# HighVBoard_01.net
KiCad netlist of a schematic drawn in EAGLE
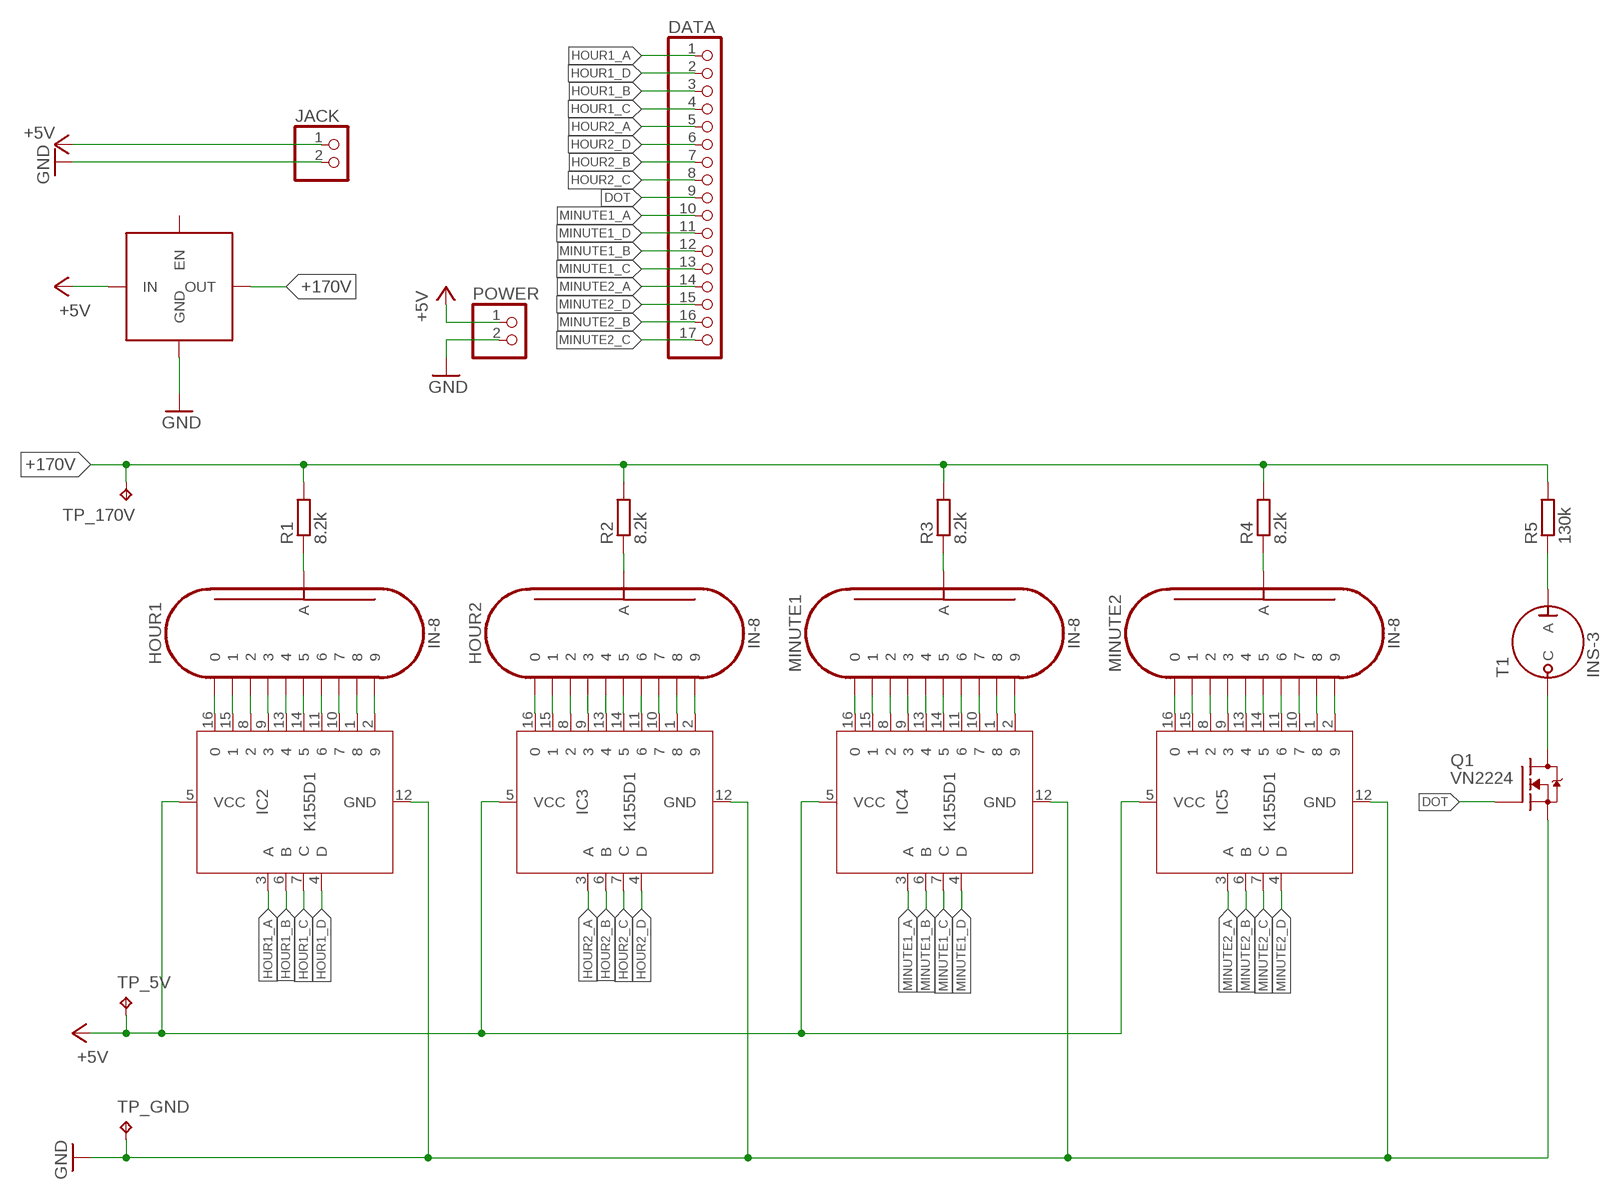
[diagram p0: schematic, sheet 1]

(export (version "E")
  (design (tool "Eeschema 10.0.6"))
  (components
    (comp (ref "DATA")
      (value "PINHD-1X17")
      (footprint "eagle-import:1X17")
      (libsource (lib "eagle-import") (part "PINHD-1X17"))
    )
    (comp (ref "HOUR1")
      (value "IN-8")
      (footprint "eagle-import:IN-8")
      (libsource (lib "eagle-import") (part "IN-8"))
    )
    (comp (ref "HOUR2")
      (value "IN-8")
      (footprint "eagle-import:IN-8")
      (libsource (lib "eagle-import") (part "IN-8"))
    )
    (comp (ref "IC2")
      (value "K155D1")
      (footprint "eagle-import:DIL16")
      (libsource (lib "eagle-import") (part "K155D1"))
    )
    (comp (ref "IC3")
      (value "K155D1")
      (footprint "eagle-import:DIL16")
      (libsource (lib "eagle-import") (part "K155D1"))
    )
    (comp (ref "IC4")
      (value "K155D1")
      (footprint "eagle-import:DIL16")
      (libsource (lib "eagle-import") (part "K155D1"))
    )
    (comp (ref "IC5")
      (value "K155D1")
      (footprint "eagle-import:DIL16")
      (libsource (lib "eagle-import") (part "K155D1"))
    )
    (comp (ref "JACK")
      (value "PINHD-1X2/90")
      (footprint "eagle-import:1X02_90")
      (libsource (lib "eagle-import") (part "PINHD-1X2/90"))
    )
    (comp (ref "MINUTE1")
      (value "IN-8")
      (footprint "eagle-import:IN-8")
      (libsource (lib "eagle-import") (part "IN-8"))
    )
    (comp (ref "MINUTE2")
      (value "IN-8")
      (footprint "eagle-import:IN-8")
      (libsource (lib "eagle-import") (part "IN-8"))
    )
    (comp (ref "POWER")
      (value "PINHD-1X2")
      (footprint "eagle-import:1X02")
      (libsource (lib "eagle-import") (part "PINHD-1X2"))
    )
    (comp (ref "Q1")
      (value "VN2224")
      (footprint "eagle-import:TO92")
      (libsource (lib "eagle-import") (part "VN2224"))
    )
    (comp (ref "R1")
      (value "8.2k")
      (footprint "eagle-import:0207_10")
      (libsource (lib "eagle-import") (part "R-EU_0207/10"))
    )
    (comp (ref "R2")
      (value "8.2k")
      (footprint "eagle-import:0207_10")
      (libsource (lib "eagle-import") (part "R-EU_0207/10"))
    )
    (comp (ref "R3")
      (value "8.2k")
      (footprint "eagle-import:0207_10")
      (libsource (lib "eagle-import") (part "R-EU_0207/10"))
    )
    (comp (ref "R4")
      (value "8.2k")
      (footprint "eagle-import:0207_10")
      (libsource (lib "eagle-import") (part "R-EU_0207/10"))
    )
    (comp (ref "R5")
      (value "130k")
      (footprint "eagle-import:0207_10")
      (libsource (lib "eagle-import") (part "R-EU_0207/10"))
    )
    (comp (ref "T1")
      (value "INS-3")
      (footprint "eagle-import:INS-3")
      (libsource (lib "eagle-import") (part "INS-3"))
    )
    (comp (ref "TP_5V")
      (value "TPPAD1-13")
      (footprint "eagle-import:P1-13")
      (libsource (lib "eagle-import") (part "TPPAD1-13"))
    )
    (comp (ref "TP_170V")
      (value "TPPAD1-13")
      (footprint "eagle-import:P1-13")
      (libsource (lib "eagle-import") (part "TPPAD1-13"))
    )
    (comp (ref "TP_GND")
      (value "TPPAD1-13")
      (footprint "eagle-import:P1-13")
      (libsource (lib "eagle-import") (part "TPPAD1-13"))
    )
    (comp (ref "U$1")
      (value "NIXIE-PSU")
      (footprint "eagle-import:NIXIE-PSU")
      (libsource (lib "eagle-import") (part "NIXIE-PSU"))
    )
  )
  (nets
    (net (code "1") (name "+5V") (class "Default")
      (node (ref "IC2") (pin "5") (pinfunction "VCC_5") (pintype "bidirectional"))
      (node (ref "IC3") (pin "5") (pinfunction "VCC_5") (pintype "bidirectional"))
      (node (ref "IC4") (pin "5") (pinfunction "VCC_5") (pintype "bidirectional"))
      (node (ref "IC5") (pin "5") (pinfunction "VCC_5") (pintype "bidirectional"))
      (node (ref "JACK") (pin "1") (pinfunction "1_1") (pintype "passive"))
      (node (ref "POWER") (pin "1") (pinfunction "1_1") (pintype "passive"))
      (node (ref "TP_5V") (pin "TP") (pinfunction "TP_TP") (pintype "input"))
      (node (ref "U$1") (pin "1") (pinfunction "IN_1") (pintype "bidirectional"))
    )
    (net (code "2") (name "+170V") (class "Default")
      (node (ref "R1") (pin "2") (pinfunction "2_2") (pintype "passive"))
      (node (ref "R2") (pin "2") (pinfunction "2_2") (pintype "passive"))
      (node (ref "R3") (pin "2") (pinfunction "2_2") (pintype "passive"))
      (node (ref "R4") (pin "2") (pinfunction "2_2") (pintype "passive"))
      (node (ref "R5") (pin "2") (pinfunction "2_2") (pintype "passive"))
      (node (ref "TP_170V") (pin "TP") (pinfunction "TP_TP") (pintype "input"))
      (node (ref "U$1") (pin "5") (pinfunction "OUT_5") (pintype "bidirectional"))
    )
    (net (code "3") (name "DOT") (class "Default")
      (node (ref "DATA") (pin "9") (pinfunction "9_9") (pintype "passive"))
      (node (ref "Q1") (pin "2") (pinfunction "G_2") (pintype "passive"))
    )
    (net (code "4") (name "GND") (class "Default")
      (node (ref "IC2") (pin "12") (pinfunction "GND_12") (pintype "bidirectional"))
      (node (ref "IC3") (pin "12") (pinfunction "GND_12") (pintype "bidirectional"))
      (node (ref "IC4") (pin "12") (pinfunction "GND_12") (pintype "bidirectional"))
      (node (ref "IC5") (pin "12") (pinfunction "GND_12") (pintype "bidirectional"))
      (node (ref "JACK") (pin "2") (pinfunction "2_2") (pintype "passive"))
      (node (ref "POWER") (pin "2") (pinfunction "2_2") (pintype "passive"))
      (node (ref "Q1") (pin "1") (pinfunction "S_1") (pintype "passive"))
      (node (ref "TP_GND") (pin "TP") (pinfunction "TP_TP") (pintype "input"))
      (node (ref "U$1") (pin "2") (pinfunction "GND_2") (pintype "bidirectional"))
      (node (ref "U$1") (pin "4") (pinfunction "GND_4") (pintype "bidirectional"))
    )
    (net (code "5") (name "HOUR1_A") (class "Default")
      (node (ref "DATA") (pin "1") (pinfunction "1_1") (pintype "passive"))
      (node (ref "IC2") (pin "3") (pinfunction "A_3") (pintype "bidirectional"))
    )
    (net (code "6") (name "HOUR1_B") (class "Default")
      (node (ref "DATA") (pin "3") (pinfunction "3_3") (pintype "passive"))
      (node (ref "IC2") (pin "6") (pinfunction "B_6") (pintype "bidirectional"))
    )
    (net (code "7") (name "HOUR1_C") (class "Default")
      (node (ref "DATA") (pin "4") (pinfunction "4_4") (pintype "passive"))
      (node (ref "IC2") (pin "7") (pinfunction "C_7") (pintype "bidirectional"))
    )
    (net (code "8") (name "HOUR1_D") (class "Default")
      (node (ref "DATA") (pin "2") (pinfunction "2_2") (pintype "passive"))
      (node (ref "IC2") (pin "4") (pinfunction "D_4") (pintype "bidirectional"))
    )
    (net (code "9") (name "HOUR2_A") (class "Default")
      (node (ref "DATA") (pin "5") (pinfunction "5_5") (pintype "passive"))
      (node (ref "IC3") (pin "3") (pinfunction "A_3") (pintype "bidirectional"))
    )
    (net (code "10") (name "HOUR2_B") (class "Default")
      (node (ref "DATA") (pin "7") (pinfunction "7_7") (pintype "passive"))
      (node (ref "IC3") (pin "6") (pinfunction "B_6") (pintype "bidirectional"))
    )
    (net (code "11") (name "HOUR2_C") (class "Default")
      (node (ref "DATA") (pin "8") (pinfunction "8_8") (pintype "passive"))
      (node (ref "IC3") (pin "7") (pinfunction "C_7") (pintype "bidirectional"))
    )
    (net (code "12") (name "HOUR2_D") (class "Default")
      (node (ref "DATA") (pin "6") (pinfunction "6_6") (pintype "passive"))
      (node (ref "IC3") (pin "4") (pinfunction "D_4") (pintype "bidirectional"))
    )
    (net (code "13") (name "MINUTE1_A") (class "Default")
      (node (ref "DATA") (pin "10") (pinfunction "10_10") (pintype "passive"))
      (node (ref "IC4") (pin "3") (pinfunction "A_3") (pintype "bidirectional"))
    )
    (net (code "14") (name "MINUTE1_B") (class "Default")
      (node (ref "DATA") (pin "12") (pinfunction "12_12") (pintype "passive"))
      (node (ref "IC4") (pin "6") (pinfunction "B_6") (pintype "bidirectional"))
    )
    (net (code "15") (name "MINUTE1_C") (class "Default")
      (node (ref "DATA") (pin "13") (pinfunction "13_13") (pintype "passive"))
      (node (ref "IC4") (pin "7") (pinfunction "C_7") (pintype "bidirectional"))
    )
    (net (code "16") (name "MINUTE1_D") (class "Default")
      (node (ref "DATA") (pin "11") (pinfunction "11_11") (pintype "passive"))
      (node (ref "IC4") (pin "4") (pinfunction "D_4") (pintype "bidirectional"))
    )
    (net (code "17") (name "MINUTE2_A") (class "Default")
      (node (ref "DATA") (pin "14") (pinfunction "14_14") (pintype "passive"))
      (node (ref "IC5") (pin "3") (pinfunction "A_3") (pintype "bidirectional"))
    )
    (net (code "18") (name "MINUTE2_B") (class "Default")
      (node (ref "DATA") (pin "16") (pinfunction "16_16") (pintype "passive"))
      (node (ref "IC5") (pin "6") (pinfunction "B_6") (pintype "bidirectional"))
    )
    (net (code "19") (name "MINUTE2_C") (class "Default")
      (node (ref "DATA") (pin "17") (pinfunction "17_17") (pintype "passive"))
      (node (ref "IC5") (pin "7") (pinfunction "C_7") (pintype "bidirectional"))
    )
    (net (code "20") (name "MINUTE2_D") (class "Default")
      (node (ref "DATA") (pin "15") (pinfunction "15_15") (pintype "passive"))
      (node (ref "IC5") (pin "4") (pinfunction "D_4") (pintype "bidirectional"))
    )
    (net (code "21") (name "Net-(HOUR1-0)") (class "Default")
      (node (ref "HOUR1") (pin "10") (pinfunction "0_10") (pintype "bidirectional"))
      (node (ref "IC2") (pin "16") (pinfunction "0_16") (pintype "bidirectional"))
    )
    (net (code "22") (name "Net-(HOUR1-PadA)") (class "Default")
      (node (ref "HOUR1") (pin "A") (pinfunction "A_A") (pintype "bidirectional"))
      (node (ref "R1") (pin "1") (pinfunction "1_1") (pintype "passive"))
    )
    (net (code "23") (name "Net-(HOUR2-0)") (class "Default")
      (node (ref "HOUR2") (pin "10") (pinfunction "0_10") (pintype "bidirectional"))
      (node (ref "IC3") (pin "16") (pinfunction "0_16") (pintype "bidirectional"))
    )
    (net (code "24") (name "Net-(HOUR2-PadA)") (class "Default")
      (node (ref "HOUR2") (pin "A") (pinfunction "A_A") (pintype "bidirectional"))
      (node (ref "R2") (pin "1") (pinfunction "1_1") (pintype "passive"))
    )
    (net (code "25") (name "Net-(IC2-1)") (class "Default")
      (node (ref "HOUR1") (pin "1") (pinfunction "1_1") (pintype "bidirectional"))
      (node (ref "IC2") (pin "15") (pinfunction "1_15") (pintype "bidirectional"))
    )
    (net (code "26") (name "Net-(IC2-2)") (class "Default")
      (node (ref "HOUR1") (pin "2") (pinfunction "2_2") (pintype "bidirectional"))
      (node (ref "IC2") (pin "8") (pinfunction "2_8") (pintype "bidirectional"))
    )
    (net (code "27") (name "Net-(IC2-3)") (class "Default")
      (node (ref "HOUR1") (pin "3") (pinfunction "3_3") (pintype "bidirectional"))
      (node (ref "IC2") (pin "9") (pinfunction "3_9") (pintype "bidirectional"))
    )
    (net (code "28") (name "Net-(IC2-4)") (class "Default")
      (node (ref "HOUR1") (pin "4") (pinfunction "4_4") (pintype "bidirectional"))
      (node (ref "IC2") (pin "13") (pinfunction "4_13") (pintype "bidirectional"))
    )
    (net (code "29") (name "Net-(IC2-5)") (class "Default")
      (node (ref "HOUR1") (pin "5") (pinfunction "5_5") (pintype "bidirectional"))
      (node (ref "IC2") (pin "14") (pinfunction "5_14") (pintype "bidirectional"))
    )
    (net (code "30") (name "Net-(IC2-6)") (class "Default")
      (node (ref "HOUR1") (pin "6") (pinfunction "6_6") (pintype "bidirectional"))
      (node (ref "IC2") (pin "11") (pinfunction "6_11") (pintype "bidirectional"))
    )
    (net (code "31") (name "Net-(IC2-7)") (class "Default")
      (node (ref "HOUR1") (pin "7") (pinfunction "7_7") (pintype "bidirectional"))
      (node (ref "IC2") (pin "10") (pinfunction "7_10") (pintype "bidirectional"))
    )
    (net (code "32") (name "Net-(IC2-8)") (class "Default")
      (node (ref "HOUR1") (pin "8") (pinfunction "8_8") (pintype "bidirectional"))
      (node (ref "IC2") (pin "1") (pinfunction "8_1") (pintype "bidirectional"))
    )
    (net (code "33") (name "Net-(IC2-9)") (class "Default")
      (node (ref "HOUR1") (pin "9") (pinfunction "9_9") (pintype "bidirectional"))
      (node (ref "IC2") (pin "2") (pinfunction "9_2") (pintype "bidirectional"))
    )
    (net (code "34") (name "Net-(IC3-1)") (class "Default")
      (node (ref "HOUR2") (pin "1") (pinfunction "1_1") (pintype "bidirectional"))
      (node (ref "IC3") (pin "15") (pinfunction "1_15") (pintype "bidirectional"))
    )
    (net (code "35") (name "Net-(IC3-2)") (class "Default")
      (node (ref "HOUR2") (pin "2") (pinfunction "2_2") (pintype "bidirectional"))
      (node (ref "IC3") (pin "8") (pinfunction "2_8") (pintype "bidirectional"))
    )
    (net (code "36") (name "Net-(IC3-3)") (class "Default")
      (node (ref "HOUR2") (pin "3") (pinfunction "3_3") (pintype "bidirectional"))
      (node (ref "IC3") (pin "9") (pinfunction "3_9") (pintype "bidirectional"))
    )
    (net (code "37") (name "Net-(IC3-4)") (class "Default")
      (node (ref "HOUR2") (pin "4") (pinfunction "4_4") (pintype "bidirectional"))
      (node (ref "IC3") (pin "13") (pinfunction "4_13") (pintype "bidirectional"))
    )
    (net (code "38") (name "Net-(IC3-5)") (class "Default")
      (node (ref "HOUR2") (pin "5") (pinfunction "5_5") (pintype "bidirectional"))
      (node (ref "IC3") (pin "14") (pinfunction "5_14") (pintype "bidirectional"))
    )
    (net (code "39") (name "Net-(IC3-6)") (class "Default")
      (node (ref "HOUR2") (pin "6") (pinfunction "6_6") (pintype "bidirectional"))
      (node (ref "IC3") (pin "11") (pinfunction "6_11") (pintype "bidirectional"))
    )
    (net (code "40") (name "Net-(IC3-7)") (class "Default")
      (node (ref "HOUR2") (pin "7") (pinfunction "7_7") (pintype "bidirectional"))
      (node (ref "IC3") (pin "10") (pinfunction "7_10") (pintype "bidirectional"))
    )
    (net (code "41") (name "Net-(IC3-8)") (class "Default")
      (node (ref "HOUR2") (pin "8") (pinfunction "8_8") (pintype "bidirectional"))
      (node (ref "IC3") (pin "1") (pinfunction "8_1") (pintype "bidirectional"))
    )
    (net (code "42") (name "Net-(IC3-9)") (class "Default")
      (node (ref "HOUR2") (pin "9") (pinfunction "9_9") (pintype "bidirectional"))
      (node (ref "IC3") (pin "2") (pinfunction "9_2") (pintype "bidirectional"))
    )
    (net (code "43") (name "Net-(IC4-0)") (class "Default")
      (node (ref "IC4") (pin "16") (pinfunction "0_16") (pintype "bidirectional"))
      (node (ref "MINUTE1") (pin "10") (pinfunction "0_10") (pintype "bidirectional"))
    )
    (net (code "44") (name "Net-(IC4-1)") (class "Default")
      (node (ref "IC4") (pin "15") (pinfunction "1_15") (pintype "bidirectional"))
      (node (ref "MINUTE1") (pin "1") (pinfunction "1_1") (pintype "bidirectional"))
    )
    (net (code "45") (name "Net-(IC4-2)") (class "Default")
      (node (ref "IC4") (pin "8") (pinfunction "2_8") (pintype "bidirectional"))
      (node (ref "MINUTE1") (pin "2") (pinfunction "2_2") (pintype "bidirectional"))
    )
    (net (code "46") (name "Net-(IC4-3)") (class "Default")
      (node (ref "IC4") (pin "9") (pinfunction "3_9") (pintype "bidirectional"))
      (node (ref "MINUTE1") (pin "3") (pinfunction "3_3") (pintype "bidirectional"))
    )
    (net (code "47") (name "Net-(IC4-4)") (class "Default")
      (node (ref "IC4") (pin "13") (pinfunction "4_13") (pintype "bidirectional"))
      (node (ref "MINUTE1") (pin "4") (pinfunction "4_4") (pintype "bidirectional"))
    )
    (net (code "48") (name "Net-(IC4-5)") (class "Default")
      (node (ref "IC4") (pin "14") (pinfunction "5_14") (pintype "bidirectional"))
      (node (ref "MINUTE1") (pin "5") (pinfunction "5_5") (pintype "bidirectional"))
    )
    (net (code "49") (name "Net-(IC4-6)") (class "Default")
      (node (ref "IC4") (pin "11") (pinfunction "6_11") (pintype "bidirectional"))
      (node (ref "MINUTE1") (pin "6") (pinfunction "6_6") (pintype "bidirectional"))
    )
    (net (code "50") (name "Net-(IC4-7)") (class "Default")
      (node (ref "IC4") (pin "10") (pinfunction "7_10") (pintype "bidirectional"))
      (node (ref "MINUTE1") (pin "7") (pinfunction "7_7") (pintype "bidirectional"))
    )
    (net (code "51") (name "Net-(IC4-8)") (class "Default")
      (node (ref "IC4") (pin "1") (pinfunction "8_1") (pintype "bidirectional"))
      (node (ref "MINUTE1") (pin "8") (pinfunction "8_8") (pintype "bidirectional"))
    )
    (net (code "52") (name "Net-(IC4-9)") (class "Default")
      (node (ref "IC4") (pin "2") (pinfunction "9_2") (pintype "bidirectional"))
      (node (ref "MINUTE1") (pin "9") (pinfunction "9_9") (pintype "bidirectional"))
    )
    (net (code "53") (name "Net-(IC5-0)") (class "Default")
      (node (ref "IC5") (pin "16") (pinfunction "0_16") (pintype "bidirectional"))
      (node (ref "MINUTE2") (pin "10") (pinfunction "0_10") (pintype "bidirectional"))
    )
    (net (code "54") (name "Net-(IC5-1)") (class "Default")
      (node (ref "IC5") (pin "15") (pinfunction "1_15") (pintype "bidirectional"))
      (node (ref "MINUTE2") (pin "1") (pinfunction "1_1") (pintype "bidirectional"))
    )
    (net (code "55") (name "Net-(IC5-2)") (class "Default")
      (node (ref "IC5") (pin "8") (pinfunction "2_8") (pintype "bidirectional"))
      (node (ref "MINUTE2") (pin "2") (pinfunction "2_2") (pintype "bidirectional"))
    )
    (net (code "56") (name "Net-(IC5-3)") (class "Default")
      (node (ref "IC5") (pin "9") (pinfunction "3_9") (pintype "bidirectional"))
      (node (ref "MINUTE2") (pin "3") (pinfunction "3_3") (pintype "bidirectional"))
    )
    (net (code "57") (name "Net-(IC5-4)") (class "Default")
      (node (ref "IC5") (pin "13") (pinfunction "4_13") (pintype "bidirectional"))
      (node (ref "MINUTE2") (pin "4") (pinfunction "4_4") (pintype "bidirectional"))
    )
    (net (code "58") (name "Net-(IC5-5)") (class "Default")
      (node (ref "IC5") (pin "14") (pinfunction "5_14") (pintype "bidirectional"))
      (node (ref "MINUTE2") (pin "5") (pinfunction "5_5") (pintype "bidirectional"))
    )
    (net (code "59") (name "Net-(IC5-6)") (class "Default")
      (node (ref "IC5") (pin "11") (pinfunction "6_11") (pintype "bidirectional"))
      (node (ref "MINUTE2") (pin "6") (pinfunction "6_6") (pintype "bidirectional"))
    )
    (net (code "60") (name "Net-(IC5-7)") (class "Default")
      (node (ref "IC5") (pin "10") (pinfunction "7_10") (pintype "bidirectional"))
      (node (ref "MINUTE2") (pin "7") (pinfunction "7_7") (pintype "bidirectional"))
    )
    (net (code "61") (name "Net-(IC5-8)") (class "Default")
      (node (ref "IC5") (pin "1") (pinfunction "8_1") (pintype "bidirectional"))
      (node (ref "MINUTE2") (pin "8") (pinfunction "8_8") (pintype "bidirectional"))
    )
    (net (code "62") (name "Net-(IC5-9)") (class "Default")
      (node (ref "IC5") (pin "2") (pinfunction "9_2") (pintype "bidirectional"))
      (node (ref "MINUTE2") (pin "9") (pinfunction "9_9") (pintype "bidirectional"))
    )
    (net (code "63") (name "Net-(MINUTE1-PadA)") (class "Default")
      (node (ref "MINUTE1") (pin "A") (pinfunction "A_A") (pintype "bidirectional"))
      (node (ref "R3") (pin "1") (pinfunction "1_1") (pintype "passive"))
    )
    (net (code "64") (name "Net-(MINUTE2-PadA)") (class "Default")
      (node (ref "MINUTE2") (pin "A") (pinfunction "A_A") (pintype "bidirectional"))
      (node (ref "R4") (pin "1") (pinfunction "1_1") (pintype "passive"))
    )
    (net (code "65") (name "Net-(Q1-D)") (class "Default")
      (node (ref "Q1") (pin "3") (pinfunction "D_3") (pintype "passive"))
      (node (ref "T1") (pin "C") (pinfunction "C_C") (pintype "bidirectional"))
    )
    (net (code "66") (name "Net-(R5-Pad1)") (class "Default")
      (node (ref "R5") (pin "1") (pinfunction "1_1") (pintype "passive"))
      (node (ref "T1") (pin "A") (pinfunction "A_A") (pintype "bidirectional"))
    )
    (net (code "67") (name "unconnected-(U$1-EN-Pad3)") (class "Default")
      (node (ref "U$1") (pin "3") (pinfunction "EN_3") (pintype "bidirectional"))
    )
  )
)
